# DevBoard.net
KiCad netlist of a schematic drawn in EAGLE
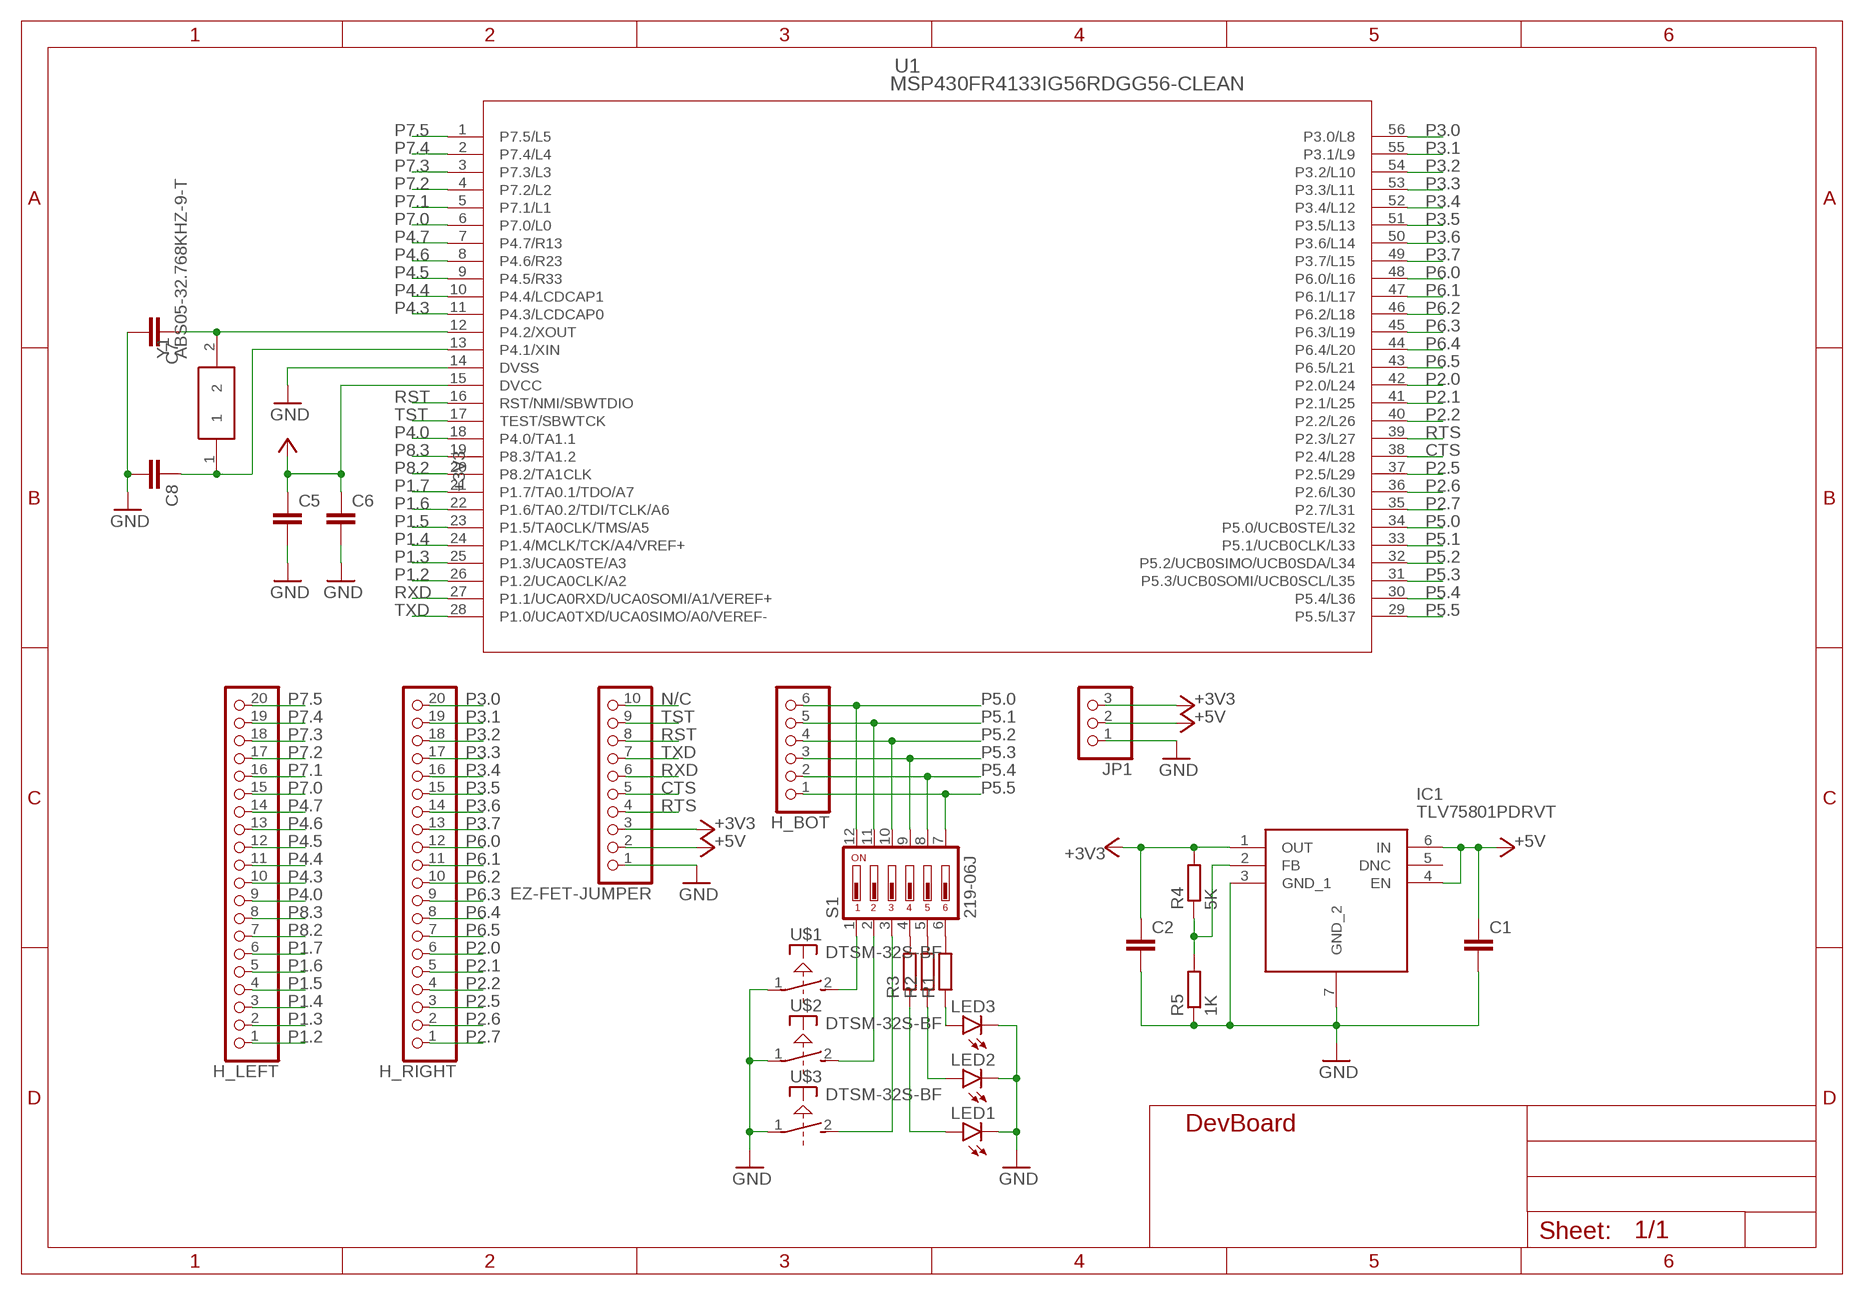
[diagram p0: schematic, sheet 1]

(export (version "E")
  (design (tool "Eeschema 10.0.6"))
  (components
    (comp (ref "C1")
      (value "C-EUC0805K")
      (footprint "eagle-import:C0805K")
      (libsource (lib "eagle-import") (part "C-EUC0805K"))
    )
    (comp (ref "C2")
      (value "C-EUC0805K")
      (footprint "eagle-import:C0805K")
      (libsource (lib "eagle-import") (part "C-EUC0805K"))
    )
    (comp (ref "C5")
      (value "C-EUC0805K")
      (footprint "eagle-import:C0805K")
      (libsource (lib "eagle-import") (part "C-EUC0805K"))
    )
    (comp (ref "C6")
      (value "C-EUC0805K")
      (footprint "eagle-import:C0805K")
      (libsource (lib "eagle-import") (part "C-EUC0805K"))
    )
    (comp (ref "C7")
      (value "C-EUC0805K")
      (footprint "eagle-import:C0805K")
      (libsource (lib "eagle-import") (part "C-EUC0805K"))
    )
    (comp (ref "C8")
      (value "C-EUC0805K")
      (footprint "eagle-import:C0805K")
      (libsource (lib "eagle-import") (part "C-EUC0805K"))
    )
    (comp (ref "EZ-FET-JUMPER")
      (value "PINHD-1X10")
      (footprint "eagle-import:1X10")
      (libsource (lib "eagle-import") (part "PINHD-1X10"))
    )
    (comp (ref "H_BOT")
      (value "PINHD-1X6")
      (footprint "eagle-import:1X06")
      (libsource (lib "eagle-import") (part "PINHD-1X6"))
    )
    (comp (ref "H_LEFT")
      (value "PINHD-1X20")
      (footprint "eagle-import:1X20")
      (libsource (lib "eagle-import") (part "PINHD-1X20"))
    )
    (comp (ref "H_RIGHT")
      (value "PINHD-1X20")
      (footprint "eagle-import:1X20")
      (libsource (lib "eagle-import") (part "PINHD-1X20"))
    )
    (comp (ref "IC1")
      (value "TLV75801PDRVT")
      (footprint "eagle-import:SON65P200X200X80-7N")
      (fields (field (name "MOUSER_PART_NUMBER") "595-TLV75801PDRVT"))
      (libsource (lib "eagle-import") (part "TLV75801PDRVT"))
    )
    (comp (ref "JP1")
      (value "PINHD-1X3")
      (footprint "eagle-import:1X03")
      (libsource (lib "eagle-import") (part "PINHD-1X3"))
    )
    (comp (ref "LED1")
      (value "LEDCHIP-LED0805")
      (footprint "eagle-import:CHIP-LED0805")
      (libsource (lib "eagle-import") (part "LEDCHIP-LED0805"))
    )
    (comp (ref "LED2")
      (value "LEDCHIP-LED0805")
      (footprint "eagle-import:CHIP-LED0805")
      (libsource (lib "eagle-import") (part "LEDCHIP-LED0805"))
    )
    (comp (ref "LED3")
      (value "LEDCHIP-LED0805")
      (footprint "eagle-import:CHIP-LED0805")
      (libsource (lib "eagle-import") (part "LEDCHIP-LED0805"))
    )
    (comp (ref "R1")
      (value "R-EU_R0805")
      (footprint "eagle-import:R0805")
      (libsource (lib "eagle-import") (part "R-EU_R0805"))
    )
    (comp (ref "R2")
      (value "R-EU_R0805")
      (footprint "eagle-import:R0805")
      (libsource (lib "eagle-import") (part "R-EU_R0805"))
    )
    (comp (ref "R3")
      (value "R-EU_R0805")
      (footprint "eagle-import:R0805")
      (libsource (lib "eagle-import") (part "R-EU_R0805"))
    )
    (comp (ref "R4")
      (value "5K")
      (footprint "eagle-import:R0805")
      (libsource (lib "eagle-import") (part "R-EU_R0805"))
    )
    (comp (ref "R5")
      (value "1K")
      (footprint "eagle-import:R0805")
      (libsource (lib "eagle-import") (part "R-EU_R0805"))
    )
    (comp (ref "S1")
      (value "219-06J")
      (footprint "eagle-import:CTS-219-06J")
      (libsource (lib "eagle-import") (part "219-06J"))
    )
    (comp (ref "U$1")
      (value "DTSM-32S-BF")
      (footprint "eagle-import:DTSM32SBF")
      (libsource (lib "eagle-import") (part "DTSM-32S-BF"))
    )
    (comp (ref "U$2")
      (value "DTSM-32S-BF")
      (footprint "eagle-import:DTSM32SBF")
      (libsource (lib "eagle-import") (part "DTSM-32S-BF"))
    )
    (comp (ref "U$3")
      (value "DTSM-32S-BF")
      (footprint "eagle-import:DTSM32SBF")
      (libsource (lib "eagle-import") (part "DTSM-32S-BF"))
    )
    (comp (ref "U1")
      (value "MSP430FR4133IG56RDGG56-CLEAN")
      (footprint "eagle-import:DGG56_CLEAN")
      (libsource (lib "eagle-import") (part "MSP430FR4133IG56RDGG56-CLEAN"))
    )
    (comp (ref "Y1")
      (value "ABS05-32.768KHZ-9-T")
      (footprint "eagle-import:ABS05")
      (fields (field (name "MOUSER_PART_NUMBER") "815-ABS05-32.768K9T"))
      (libsource (lib "eagle-import") (part "ABS05-32.768KHZ-9-T"))
    )
  )
  (nets
    (net (code "1") (name "+3V3") (class "Default")
      (node (ref "C2") (pin "1") (pinfunction "1_1") (pintype "passive"))
      (node (ref "C5") (pin "1") (pinfunction "1_1") (pintype "passive"))
      (node (ref "C6") (pin "1") (pinfunction "1_1") (pintype "passive"))
      (node (ref "EZ-FET-JUMPER") (pin "3") (pinfunction "3_3") (pintype "passive"))
      (node (ref "IC1") (pin "1") (pinfunction "OUT_1") (pintype "bidirectional"))
      (node (ref "JP1") (pin "3") (pinfunction "3_3") (pintype "passive"))
      (node (ref "R4") (pin "2") (pinfunction "2_2") (pintype "passive"))
      (node (ref "U1") (pin "15") (pinfunction "DVCC_15") (pintype "power_in"))
    )
    (net (code "2") (name "+5V") (class "Default")
      (node (ref "C1") (pin "1") (pinfunction "1_1") (pintype "passive"))
      (node (ref "EZ-FET-JUMPER") (pin "2") (pinfunction "2_2") (pintype "passive"))
      (node (ref "IC1") (pin "4") (pinfunction "EN_4") (pintype "bidirectional"))
      (node (ref "IC1") (pin "6") (pinfunction "IN_6") (pintype "bidirectional"))
      (node (ref "JP1") (pin "2") (pinfunction "2_2") (pintype "passive"))
    )
    (net (code "3") (name "/CTS") (class "Default")
      (node (ref "EZ-FET-JUMPER") (pin "5") (pinfunction "5_5") (pintype "passive"))
      (node (ref "U1") (pin "38") (pinfunction "P2.4/L28_38") (pintype "bidirectional"))
    )
    (net (code "4") (name "/N{slash}C") (class "Default")
      (node (ref "EZ-FET-JUMPER") (pin "10") (pinfunction "10_10") (pintype "passive"))
    )
    (net (code "5") (name "/P1.2") (class "Default")
      (node (ref "H_LEFT") (pin "1") (pinfunction "1_1") (pintype "passive"))
      (node (ref "U1") (pin "26") (pinfunction "P1.2/UCA0CLK/A2_26") (pintype "bidirectional"))
    )
    (net (code "6") (name "/P1.3") (class "Default")
      (node (ref "H_LEFT") (pin "2") (pinfunction "2_2") (pintype "passive"))
      (node (ref "U1") (pin "25") (pinfunction "P1.3/UCA0STE/A3_25") (pintype "bidirectional"))
    )
    (net (code "7") (name "/P1.4") (class "Default")
      (node (ref "H_LEFT") (pin "3") (pinfunction "3_3") (pintype "passive"))
      (node (ref "U1") (pin "24") (pinfunction "P1.4/MCLK/TCK/A4/VREF+_24") (pintype "bidirectional"))
    )
    (net (code "8") (name "/P1.5") (class "Default")
      (node (ref "H_LEFT") (pin "4") (pinfunction "4_4") (pintype "passive"))
      (node (ref "U1") (pin "23") (pinfunction "P1.5/TA0CLK/TMS/A5_23") (pintype "bidirectional"))
    )
    (net (code "9") (name "/P1.6") (class "Default")
      (node (ref "H_LEFT") (pin "5") (pinfunction "5_5") (pintype "passive"))
      (node (ref "U1") (pin "22") (pinfunction "P1.6/TA0.2/TDI/TCLK/A6_22") (pintype "bidirectional"))
    )
    (net (code "10") (name "/P1.7") (class "Default")
      (node (ref "H_LEFT") (pin "6") (pinfunction "6_6") (pintype "passive"))
      (node (ref "U1") (pin "21") (pinfunction "P1.7/TA0.1/TDO/A7_21") (pintype "bidirectional"))
    )
    (net (code "11") (name "/P2.0") (class "Default")
      (node (ref "H_RIGHT") (pin "6") (pinfunction "6_6") (pintype "passive"))
      (node (ref "U1") (pin "42") (pinfunction "P2.0/L24_42") (pintype "bidirectional"))
    )
    (net (code "12") (name "/P2.1") (class "Default")
      (node (ref "H_RIGHT") (pin "5") (pinfunction "5_5") (pintype "passive"))
      (node (ref "U1") (pin "41") (pinfunction "P2.1/L25_41") (pintype "bidirectional"))
    )
    (net (code "13") (name "/P2.2") (class "Default")
      (node (ref "H_RIGHT") (pin "4") (pinfunction "4_4") (pintype "passive"))
      (node (ref "U1") (pin "40") (pinfunction "P2.2/L26_40") (pintype "bidirectional"))
    )
    (net (code "14") (name "/P2.5") (class "Default")
      (node (ref "H_RIGHT") (pin "3") (pinfunction "3_3") (pintype "passive"))
      (node (ref "U1") (pin "37") (pinfunction "P2.5/L29_37") (pintype "bidirectional"))
    )
    (net (code "15") (name "/P2.6") (class "Default")
      (node (ref "H_RIGHT") (pin "2") (pinfunction "2_2") (pintype "passive"))
      (node (ref "U1") (pin "36") (pinfunction "P2.6/L30_36") (pintype "bidirectional"))
    )
    (net (code "16") (name "/P2.7") (class "Default")
      (node (ref "H_RIGHT") (pin "1") (pinfunction "1_1") (pintype "passive"))
      (node (ref "U1") (pin "35") (pinfunction "P2.7/L31_35") (pintype "bidirectional"))
    )
    (net (code "17") (name "/P3.0") (class "Default")
      (node (ref "H_RIGHT") (pin "20") (pinfunction "20_20") (pintype "passive"))
      (node (ref "U1") (pin "56") (pinfunction "P3.0/L8_56") (pintype "bidirectional"))
    )
    (net (code "18") (name "/P3.1") (class "Default")
      (node (ref "H_RIGHT") (pin "19") (pinfunction "19_19") (pintype "passive"))
      (node (ref "U1") (pin "55") (pinfunction "P3.1/L9_55") (pintype "bidirectional"))
    )
    (net (code "19") (name "/P3.2") (class "Default")
      (node (ref "H_RIGHT") (pin "18") (pinfunction "18_18") (pintype "passive"))
      (node (ref "U1") (pin "54") (pinfunction "P3.2/L10_54") (pintype "bidirectional"))
    )
    (net (code "20") (name "/P3.3") (class "Default")
      (node (ref "H_RIGHT") (pin "17") (pinfunction "17_17") (pintype "passive"))
      (node (ref "U1") (pin "53") (pinfunction "P3.3/L11_53") (pintype "bidirectional"))
    )
    (net (code "21") (name "/P3.4") (class "Default")
      (node (ref "H_RIGHT") (pin "16") (pinfunction "16_16") (pintype "passive"))
      (node (ref "U1") (pin "52") (pinfunction "P3.4/L12_52") (pintype "bidirectional"))
    )
    (net (code "22") (name "/P3.5") (class "Default")
      (node (ref "H_RIGHT") (pin "15") (pinfunction "15_15") (pintype "passive"))
      (node (ref "U1") (pin "51") (pinfunction "P3.5/L13_51") (pintype "bidirectional"))
    )
    (net (code "23") (name "/P3.6") (class "Default")
      (node (ref "H_RIGHT") (pin "14") (pinfunction "14_14") (pintype "passive"))
      (node (ref "U1") (pin "50") (pinfunction "P3.6/L14_50") (pintype "bidirectional"))
    )
    (net (code "24") (name "/P3.7") (class "Default")
      (node (ref "H_RIGHT") (pin "13") (pinfunction "13_13") (pintype "passive"))
      (node (ref "U1") (pin "49") (pinfunction "P3.7/L15_49") (pintype "bidirectional"))
    )
    (net (code "25") (name "/P4.0") (class "Default")
      (node (ref "H_LEFT") (pin "9") (pinfunction "9_9") (pintype "passive"))
      (node (ref "U1") (pin "18") (pinfunction "P4.0/TA1.1_18") (pintype "bidirectional"))
    )
    (net (code "26") (name "/P4.3") (class "Default")
      (node (ref "H_LEFT") (pin "10") (pinfunction "10_10") (pintype "passive"))
      (node (ref "U1") (pin "11") (pinfunction "P4.3/LCDCAP0_11") (pintype "bidirectional"))
    )
    (net (code "27") (name "/P4.4") (class "Default")
      (node (ref "H_LEFT") (pin "11") (pinfunction "11_11") (pintype "passive"))
      (node (ref "U1") (pin "10") (pinfunction "P4.4/LCDCAP1_10") (pintype "bidirectional"))
    )
    (net (code "28") (name "/P4.5") (class "Default")
      (node (ref "H_LEFT") (pin "12") (pinfunction "12_12") (pintype "passive"))
      (node (ref "U1") (pin "9") (pinfunction "P4.5/R33_9") (pintype "bidirectional"))
    )
    (net (code "29") (name "/P4.6") (class "Default")
      (node (ref "H_LEFT") (pin "13") (pinfunction "13_13") (pintype "passive"))
      (node (ref "U1") (pin "8") (pinfunction "P4.6/R23_8") (pintype "bidirectional"))
    )
    (net (code "30") (name "/P4.7") (class "Default")
      (node (ref "H_LEFT") (pin "14") (pinfunction "14_14") (pintype "passive"))
      (node (ref "U1") (pin "7") (pinfunction "P4.7/R13_7") (pintype "bidirectional"))
    )
    (net (code "31") (name "/P5.0") (class "Default")
      (node (ref "H_BOT") (pin "6") (pinfunction "6_6") (pintype "passive"))
      (node (ref "S1") (pin "12") (pinfunction "12_12") (pintype "passive"))
      (node (ref "U1") (pin "34") (pinfunction "P5.0/UCB0STE/L32_34") (pintype "bidirectional"))
    )
    (net (code "32") (name "/P5.1") (class "Default")
      (node (ref "H_BOT") (pin "5") (pinfunction "5_5") (pintype "passive"))
      (node (ref "S1") (pin "11") (pinfunction "11_11") (pintype "passive"))
      (node (ref "U1") (pin "33") (pinfunction "P5.1/UCB0CLK/L33_33") (pintype "bidirectional"))
    )
    (net (code "33") (name "/P5.2") (class "Default")
      (node (ref "H_BOT") (pin "4") (pinfunction "4_4") (pintype "passive"))
      (node (ref "S1") (pin "10") (pinfunction "10_10") (pintype "passive"))
      (node (ref "U1") (pin "32") (pinfunction "P5.2/UCB0SIMO/UCB0SDA/L34_32") (pintype "bidirectional"))
    )
    (net (code "34") (name "/P5.3") (class "Default")
      (node (ref "H_BOT") (pin "3") (pinfunction "3_3") (pintype "passive"))
      (node (ref "S1") (pin "9") (pinfunction "9_9") (pintype "passive"))
      (node (ref "U1") (pin "31") (pinfunction "P5.3/UCB0SOMI/UCB0SCL/L35_31") (pintype "bidirectional"))
    )
    (net (code "35") (name "/P5.4") (class "Default")
      (node (ref "H_BOT") (pin "2") (pinfunction "2_2") (pintype "passive"))
      (node (ref "S1") (pin "8") (pinfunction "8_8") (pintype "passive"))
      (node (ref "U1") (pin "30") (pinfunction "P5.4/L36_30") (pintype "bidirectional"))
    )
    (net (code "36") (name "/P5.5") (class "Default")
      (node (ref "H_BOT") (pin "1") (pinfunction "1_1") (pintype "passive"))
      (node (ref "S1") (pin "7") (pinfunction "7_7") (pintype "passive"))
      (node (ref "U1") (pin "29") (pinfunction "P5.5/L37_29") (pintype "bidirectional"))
    )
    (net (code "37") (name "/P6.0") (class "Default")
      (node (ref "H_RIGHT") (pin "12") (pinfunction "12_12") (pintype "passive"))
      (node (ref "U1") (pin "48") (pinfunction "P6.0/L16_48") (pintype "bidirectional"))
    )
    (net (code "38") (name "/P6.1") (class "Default")
      (node (ref "H_RIGHT") (pin "11") (pinfunction "11_11") (pintype "passive"))
      (node (ref "U1") (pin "47") (pinfunction "P6.1/L17_47") (pintype "bidirectional"))
    )
    (net (code "39") (name "/P6.2") (class "Default")
      (node (ref "H_RIGHT") (pin "10") (pinfunction "10_10") (pintype "passive"))
      (node (ref "U1") (pin "46") (pinfunction "P6.2/L18_46") (pintype "bidirectional"))
    )
    (net (code "40") (name "/P6.3") (class "Default")
      (node (ref "H_RIGHT") (pin "9") (pinfunction "9_9") (pintype "passive"))
      (node (ref "U1") (pin "45") (pinfunction "P6.3/L19_45") (pintype "bidirectional"))
    )
    (net (code "41") (name "/P6.4") (class "Default")
      (node (ref "H_RIGHT") (pin "8") (pinfunction "8_8") (pintype "passive"))
      (node (ref "U1") (pin "44") (pinfunction "P6.4/L20_44") (pintype "bidirectional"))
    )
    (net (code "42") (name "/P6.5") (class "Default")
      (node (ref "H_RIGHT") (pin "7") (pinfunction "7_7") (pintype "passive"))
      (node (ref "U1") (pin "43") (pinfunction "P6.5/L21_43") (pintype "bidirectional"))
    )
    (net (code "43") (name "/P7.0") (class "Default")
      (node (ref "H_LEFT") (pin "15") (pinfunction "15_15") (pintype "passive"))
      (node (ref "U1") (pin "6") (pinfunction "P7.0/L0_6") (pintype "bidirectional"))
    )
    (net (code "44") (name "/P7.1") (class "Default")
      (node (ref "H_LEFT") (pin "16") (pinfunction "16_16") (pintype "passive"))
      (node (ref "U1") (pin "5") (pinfunction "P7.1/L1_5") (pintype "bidirectional"))
    )
    (net (code "45") (name "/P7.2") (class "Default")
      (node (ref "H_LEFT") (pin "17") (pinfunction "17_17") (pintype "passive"))
      (node (ref "U1") (pin "4") (pinfunction "P7.2/L2_4") (pintype "bidirectional"))
    )
    (net (code "46") (name "/P7.3") (class "Default")
      (node (ref "H_LEFT") (pin "18") (pinfunction "18_18") (pintype "passive"))
      (node (ref "U1") (pin "3") (pinfunction "P7.3/L3_3") (pintype "bidirectional"))
    )
    (net (code "47") (name "/P7.4") (class "Default")
      (node (ref "H_LEFT") (pin "19") (pinfunction "19_19") (pintype "passive"))
      (node (ref "U1") (pin "2") (pinfunction "P7.4/L4_2") (pintype "bidirectional"))
    )
    (net (code "48") (name "/P7.5") (class "Default")
      (node (ref "H_LEFT") (pin "20") (pinfunction "20_20") (pintype "passive"))
      (node (ref "U1") (pin "1") (pinfunction "P7.5/L5_1") (pintype "bidirectional"))
    )
    (net (code "49") (name "/P8.2") (class "Default")
      (node (ref "H_LEFT") (pin "7") (pinfunction "7_7") (pintype "passive"))
      (node (ref "U1") (pin "20") (pinfunction "P8.2/TA1CLK_20") (pintype "bidirectional"))
    )
    (net (code "50") (name "/P8.3") (class "Default")
      (node (ref "H_LEFT") (pin "8") (pinfunction "8_8") (pintype "passive"))
      (node (ref "U1") (pin "19") (pinfunction "P8.3/TA1.2_19") (pintype "bidirectional"))
    )
    (net (code "51") (name "/RST") (class "Default")
      (node (ref "EZ-FET-JUMPER") (pin "8") (pinfunction "8_8") (pintype "passive"))
      (node (ref "U1") (pin "16") (pinfunction "RST/NMI/SBWTDIO_16") (pintype "bidirectional"))
    )
    (net (code "52") (name "/RTS") (class "Default")
      (node (ref "EZ-FET-JUMPER") (pin "4") (pinfunction "4_4") (pintype "passive"))
      (node (ref "U1") (pin "39") (pinfunction "P2.3/L27_39") (pintype "bidirectional"))
    )
    (net (code "53") (name "/RXD") (class "Default")
      (node (ref "EZ-FET-JUMPER") (pin "6") (pinfunction "6_6") (pintype "passive"))
      (node (ref "U1") (pin "27") (pinfunction "P1.1/UCA0RXD/UCA0SOMI/A1/VEREF+_27") (pintype "bidirectional"))
    )
    (net (code "54") (name "/TST") (class "Default")
      (node (ref "EZ-FET-JUMPER") (pin "9") (pinfunction "9_9") (pintype "passive"))
      (node (ref "U1") (pin "17") (pinfunction "TEST/SBWTCK_17") (pintype "input"))
    )
    (net (code "55") (name "/TXD") (class "Default")
      (node (ref "EZ-FET-JUMPER") (pin "7") (pinfunction "7_7") (pintype "passive"))
      (node (ref "U1") (pin "28") (pinfunction "P1.0/UCA0TXD/UCA0SIMO/A0/VEREF-_28") (pintype "bidirectional"))
    )
    (net (code "56") (name "GND") (class "Default")
      (node (ref "C1") (pin "2") (pinfunction "2_2") (pintype "passive"))
      (node (ref "C2") (pin "2") (pinfunction "2_2") (pintype "passive"))
      (node (ref "C5") (pin "2") (pinfunction "2_2") (pintype "passive"))
      (node (ref "C6") (pin "2") (pinfunction "2_2") (pintype "passive"))
      (node (ref "C7") (pin "2") (pinfunction "2_2") (pintype "passive"))
      (node (ref "C8") (pin "2") (pinfunction "2_2") (pintype "passive"))
      (node (ref "EZ-FET-JUMPER") (pin "1") (pinfunction "1_1") (pintype "passive"))
      (node (ref "IC1") (pin "3") (pinfunction "GND_1_3") (pintype "bidirectional"))
      (node (ref "IC1") (pin "7") (pinfunction "GND_2_7") (pintype "bidirectional"))
      (node (ref "JP1") (pin "1") (pinfunction "1_1") (pintype "passive"))
      (node (ref "LED1") (pin "C") (pinfunction "C_C") (pintype "passive"))
      (node (ref "LED2") (pin "C") (pinfunction "C_C") (pintype "passive"))
      (node (ref "LED3") (pin "C") (pinfunction "C_C") (pintype "passive"))
      (node (ref "R5") (pin "1") (pinfunction "1_1") (pintype "passive"))
      (node (ref "U$1") (pin "1") (pinfunction "P_1") (pintype "passive"))
      (node (ref "U$2") (pin "1") (pinfunction "P_1") (pintype "passive"))
      (node (ref "U$3") (pin "1") (pinfunction "P_1") (pintype "passive"))
      (node (ref "U1") (pin "14") (pinfunction "DVSS_14") (pintype "power_in"))
    )
    (net (code "57") (name "Net-(IC1-FB)") (class "Default")
      (node (ref "IC1") (pin "2") (pinfunction "FB_2") (pintype "bidirectional"))
      (node (ref "R4") (pin "1") (pinfunction "1_1") (pintype "passive"))
      (node (ref "R5") (pin "2") (pinfunction "2_2") (pintype "passive"))
    )
    (net (code "58") (name "Net-(LED1-PadA)") (class "Default")
      (node (ref "LED1") (pin "A") (pinfunction "A_A") (pintype "passive"))
      (node (ref "R3") (pin "1") (pinfunction "1_1") (pintype "passive"))
    )
    (net (code "59") (name "Net-(LED2-PadA)") (class "Default")
      (node (ref "LED2") (pin "A") (pinfunction "A_A") (pintype "passive"))
      (node (ref "R2") (pin "1") (pinfunction "1_1") (pintype "passive"))
    )
    (net (code "60") (name "Net-(LED3-PadA)") (class "Default")
      (node (ref "LED3") (pin "A") (pinfunction "A_A") (pintype "passive"))
      (node (ref "R1") (pin "1") (pinfunction "1_1") (pintype "passive"))
    )
    (net (code "61") (name "Net-(R1-Pad2)") (class "Default")
      (node (ref "R1") (pin "2") (pinfunction "2_2") (pintype "passive"))
      (node (ref "S1") (pin "6") (pinfunction "6_6") (pintype "passive"))
    )
    (net (code "62") (name "Net-(R2-Pad2)") (class "Default")
      (node (ref "R2") (pin "2") (pinfunction "2_2") (pintype "passive"))
      (node (ref "S1") (pin "5") (pinfunction "5_5") (pintype "passive"))
    )
    (net (code "63") (name "Net-(R3-Pad2)") (class "Default")
      (node (ref "R3") (pin "2") (pinfunction "2_2") (pintype "passive"))
      (node (ref "S1") (pin "4") (pinfunction "4_4") (pintype "passive"))
    )
    (net (code "64") (name "Net-(U$1-S)") (class "Default")
      (node (ref "S1") (pin "1") (pinfunction "1_1") (pintype "passive"))
      (node (ref "U$1") (pin "2") (pinfunction "S_2") (pintype "passive"))
    )
    (net (code "65") (name "Net-(U$2-S)") (class "Default")
      (node (ref "S1") (pin "2") (pinfunction "2_2") (pintype "passive"))
      (node (ref "U$2") (pin "2") (pinfunction "S_2") (pintype "passive"))
    )
    (net (code "66") (name "Net-(U$3-S)") (class "Default")
      (node (ref "S1") (pin "3") (pinfunction "3_3") (pintype "passive"))
      (node (ref "U$3") (pin "2") (pinfunction "S_2") (pintype "passive"))
    )
    (net (code "67") (name "Net-(U1-P4.1{slash}XIN)") (class "Default")
      (node (ref "C8") (pin "1") (pinfunction "1_1") (pintype "passive"))
      (node (ref "U1") (pin "13") (pinfunction "P4.1/XIN_13") (pintype "bidirectional"))
      (node (ref "Y1") (pin "1") (pinfunction "1_1") (pintype "bidirectional"))
    )
    (net (code "68") (name "Net-(U1-P4.2{slash}XOUT)") (class "Default")
      (node (ref "C7") (pin "1") (pinfunction "1_1") (pintype "passive"))
      (node (ref "U1") (pin "12") (pinfunction "P4.2/XOUT_12") (pintype "bidirectional"))
      (node (ref "Y1") (pin "2") (pinfunction "2_2") (pintype "bidirectional"))
    )
    (net (code "69") (name "unconnected-(IC1-DNC-Pad5)") (class "Default")
      (node (ref "IC1") (pin "5") (pinfunction "DNC_5") (pintype "bidirectional"))
    )
  )
)
